# JTAG.net
KiCad netlist of a schematic drawn in EAGLE
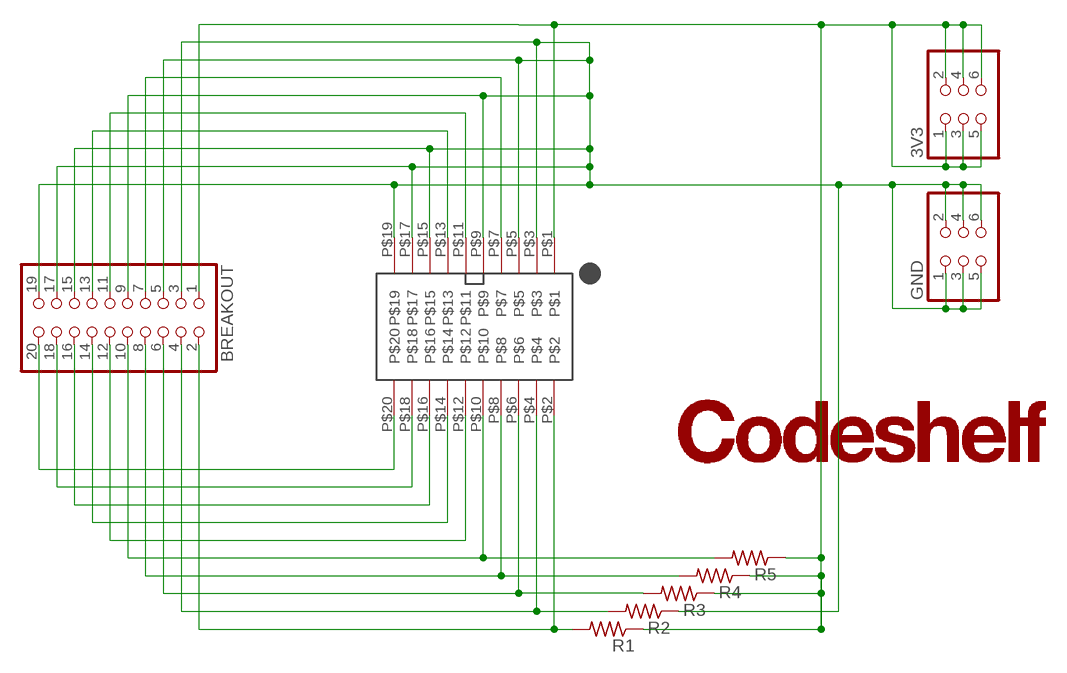
[diagram p0: schematic, sheet 1]

(export (version "E")
  (design (tool "Eeschema 10.0.6"))
  (components
    (comp (ref "3V3")
      (value "PINHD-2X3")
      (footprint "eagle-import:2X03")
      (libsource (lib "eagle-import") (part "PINHD-2X3"))
    )
    (comp (ref "BREAKOUT")
      (value "PINHD-2X10")
      (footprint "eagle-import:2X10")
      (libsource (lib "eagle-import") (part "PINHD-2X10"))
    )
    (comp (ref "GND")
      (value "PINHD-2X3")
      (footprint "eagle-import:2X03")
      (libsource (lib "eagle-import") (part "PINHD-2X3"))
    )
    (comp (ref "JTAG")
      (value "2X10JTAG")
      (footprint "eagle-import:2X10JTAG")
      (fields (field (name "MFGP") "3220-20-0100-00"))
      (libsource (lib "eagle-import") (part "2X10JTAG"))
    )
    (comp (ref "R1")
      (value "R-US_0207/10")
      (footprint "eagle-import:0207_10")
      (libsource (lib "eagle-import") (part "R-US_0207/10"))
    )
    (comp (ref "R2")
      (value "R-US_0207/10")
      (footprint "eagle-import:0207_10")
      (libsource (lib "eagle-import") (part "R-US_0207/10"))
    )
    (comp (ref "R3")
      (value "R-US_0207/10")
      (footprint "eagle-import:0207_10")
      (libsource (lib "eagle-import") (part "R-US_0207/10"))
    )
    (comp (ref "R4")
      (value "R-US_0207/10")
      (footprint "eagle-import:0207_10")
      (libsource (lib "eagle-import") (part "R-US_0207/10"))
    )
    (comp (ref "R5")
      (value "R-US_0207/10")
      (footprint "eagle-import:0207_10")
      (libsource (lib "eagle-import") (part "R-US_0207/10"))
    )
    (comp (ref "U$1")
      (value "CODESHELF-LOGOSMALL")
      (footprint "eagle-import:CODESHELF-LOGO-SMALL")
      (libsource (lib "eagle-import") (part "CODESHELF-LOGOSMALL"))
    )
  )
  (nets
    (net (code "1") (name "Net-(3V3-Pad1)") (class "Default")
      (node (ref "3V3") (pin "1") (pinfunction "1_1") (pintype "passive"))
      (node (ref "3V3") (pin "2") (pinfunction "2_2") (pintype "passive"))
      (node (ref "3V3") (pin "3") (pinfunction "3_3") (pintype "passive"))
      (node (ref "3V3") (pin "4") (pinfunction "4_4") (pintype "passive"))
      (node (ref "3V3") (pin "5") (pinfunction "5_5") (pintype "passive"))
      (node (ref "3V3") (pin "6") (pinfunction "6_6") (pintype "passive"))
      (node (ref "BREAKOUT") (pin "1") (pinfunction "1_1") (pintype "passive"))
      (node (ref "JTAG") (pin "P$1") (pinfunction "P$1_P$1") (pintype "bidirectional"))
      (node (ref "R1") (pin "1") (pinfunction "1_1") (pintype "passive"))
      (node (ref "R3") (pin "1") (pinfunction "1_1") (pintype "passive"))
      (node (ref "R4") (pin "1") (pinfunction "1_1") (pintype "passive"))
      (node (ref "R5") (pin "1") (pinfunction "1_1") (pintype "passive"))
    )
    (net (code "2") (name "Net-(BREAKOUT-Pad2)") (class "Default")
      (node (ref "BREAKOUT") (pin "2") (pinfunction "2_2") (pintype "passive"))
      (node (ref "JTAG") (pin "P$2") (pinfunction "P$2_P$2") (pintype "bidirectional"))
      (node (ref "R1") (pin "2") (pinfunction "2_2") (pintype "passive"))
    )
    (net (code "3") (name "Net-(BREAKOUT-Pad4)") (class "Default")
      (node (ref "BREAKOUT") (pin "4") (pinfunction "4_4") (pintype "passive"))
      (node (ref "JTAG") (pin "P$4") (pinfunction "P$4_P$4") (pintype "bidirectional"))
      (node (ref "R2") (pin "2") (pinfunction "2_2") (pintype "passive"))
    )
    (net (code "4") (name "Net-(BREAKOUT-Pad6)") (class "Default")
      (node (ref "BREAKOUT") (pin "6") (pinfunction "6_6") (pintype "passive"))
      (node (ref "JTAG") (pin "P$6") (pinfunction "P$6_P$6") (pintype "bidirectional"))
      (node (ref "R3") (pin "2") (pinfunction "2_2") (pintype "passive"))
    )
    (net (code "5") (name "Net-(BREAKOUT-Pad7)") (class "Default")
      (node (ref "BREAKOUT") (pin "7") (pinfunction "7_7") (pintype "passive"))
      (node (ref "JTAG") (pin "P$7") (pinfunction "P$7_P$7") (pintype "bidirectional"))
    )
    (net (code "6") (name "Net-(BREAKOUT-Pad8)") (class "Default")
      (node (ref "BREAKOUT") (pin "8") (pinfunction "8_8") (pintype "passive"))
      (node (ref "JTAG") (pin "P$8") (pinfunction "P$8_P$8") (pintype "bidirectional"))
      (node (ref "R4") (pin "2") (pinfunction "2_2") (pintype "passive"))
    )
    (net (code "7") (name "Net-(BREAKOUT-Pad10)") (class "Default")
      (node (ref "BREAKOUT") (pin "10") (pinfunction "10_10") (pintype "passive"))
      (node (ref "JTAG") (pin "P$10") (pinfunction "P$10_P$10") (pintype "bidirectional"))
      (node (ref "R5") (pin "2") (pinfunction "2_2") (pintype "passive"))
    )
    (net (code "8") (name "Net-(BREAKOUT-Pad11)") (class "Default")
      (node (ref "BREAKOUT") (pin "11") (pinfunction "11_11") (pintype "passive"))
      (node (ref "JTAG") (pin "P$11") (pinfunction "P$11_P$11") (pintype "bidirectional"))
    )
    (net (code "9") (name "Net-(BREAKOUT-Pad12)") (class "Default")
      (node (ref "BREAKOUT") (pin "12") (pinfunction "12_12") (pintype "passive"))
      (node (ref "JTAG") (pin "P$12") (pinfunction "P$12_P$12") (pintype "bidirectional"))
    )
    (net (code "10") (name "Net-(BREAKOUT-Pad13)") (class "Default")
      (node (ref "BREAKOUT") (pin "13") (pinfunction "13_13") (pintype "passive"))
      (node (ref "JTAG") (pin "P$13") (pinfunction "P$13_P$13") (pintype "bidirectional"))
    )
    (net (code "11") (name "Net-(BREAKOUT-Pad14)") (class "Default")
      (node (ref "BREAKOUT") (pin "14") (pinfunction "14_14") (pintype "passive"))
      (node (ref "JTAG") (pin "P$14") (pinfunction "P$14_P$14") (pintype "bidirectional"))
    )
    (net (code "12") (name "Net-(BREAKOUT-Pad15)") (class "Default")
      (node (ref "BREAKOUT") (pin "15") (pinfunction "15_15") (pintype "passive"))
      (node (ref "BREAKOUT") (pin "17") (pinfunction "17_17") (pintype "passive"))
      (node (ref "BREAKOUT") (pin "19") (pinfunction "19_19") (pintype "passive"))
      (node (ref "BREAKOUT") (pin "3") (pinfunction "3_3") (pintype "passive"))
      (node (ref "BREAKOUT") (pin "5") (pinfunction "5_5") (pintype "passive"))
      (node (ref "BREAKOUT") (pin "9") (pinfunction "9_9") (pintype "passive"))
      (node (ref "GND") (pin "1") (pinfunction "1_1") (pintype "passive"))
      (node (ref "GND") (pin "2") (pinfunction "2_2") (pintype "passive"))
      (node (ref "GND") (pin "3") (pinfunction "3_3") (pintype "passive"))
      (node (ref "GND") (pin "4") (pinfunction "4_4") (pintype "passive"))
      (node (ref "GND") (pin "5") (pinfunction "5_5") (pintype "passive"))
      (node (ref "GND") (pin "6") (pinfunction "6_6") (pintype "passive"))
      (node (ref "JTAG") (pin "P$15") (pinfunction "P$15_P$15") (pintype "bidirectional"))
      (node (ref "JTAG") (pin "P$17") (pinfunction "P$17_P$17") (pintype "bidirectional"))
      (node (ref "JTAG") (pin "P$19") (pinfunction "P$19_P$19") (pintype "bidirectional"))
      (node (ref "JTAG") (pin "P$3") (pinfunction "P$3_P$3") (pintype "bidirectional"))
      (node (ref "JTAG") (pin "P$5") (pinfunction "P$5_P$5") (pintype "bidirectional"))
      (node (ref "JTAG") (pin "P$9") (pinfunction "P$9_P$9") (pintype "bidirectional"))
      (node (ref "R2") (pin "1") (pinfunction "1_1") (pintype "passive"))
    )
    (net (code "13") (name "Net-(BREAKOUT-Pad16)") (class "Default")
      (node (ref "BREAKOUT") (pin "16") (pinfunction "16_16") (pintype "passive"))
      (node (ref "JTAG") (pin "P$16") (pinfunction "P$16_P$16") (pintype "bidirectional"))
    )
    (net (code "14") (name "Net-(BREAKOUT-Pad18)") (class "Default")
      (node (ref "BREAKOUT") (pin "18") (pinfunction "18_18") (pintype "passive"))
      (node (ref "JTAG") (pin "P$18") (pinfunction "P$18_P$18") (pintype "bidirectional"))
    )
    (net (code "15") (name "Net-(BREAKOUT-Pad20)") (class "Default")
      (node (ref "BREAKOUT") (pin "20") (pinfunction "20_20") (pintype "passive"))
      (node (ref "JTAG") (pin "P$20") (pinfunction "P$20_P$20") (pintype "bidirectional"))
    )
  )
)
